# 4_TB6612_1_schdoc.net
KiCad netlist of a schematic drawn in Altium Designer
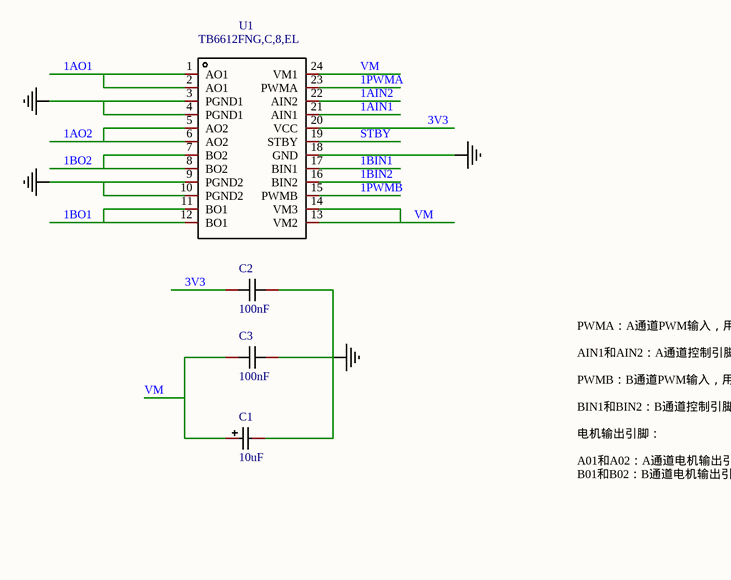
[diagram p0: 4_TB6612（1）.schdoc.schdoc]

(export (version "E")
  (design (tool "Eeschema 10.0.6"))
  (components
    (comp (ref "C1")
      (value "10uF")
      (fields
        (field (name "NAME") "10uF")
        (field (name "MANUFACTURER") "Kyocera AVX")
        (field (name "MANUFACTURER PART") "TAJB106K025RNJ")
        (field (name "TOLERANCE") "±10%")
      )
      (libsource (lib "altium-import") (part "root_2_TAJB106K025RNJ_"))
    )
    (comp (ref "C2")
      (value "100nF")
      (fields (field (name "NAME") "100nF"))
      (libsource (lib "altium-import") (part "root_0_CAP_0603_"))
    )
    (comp (ref "C3")
      (value "100nF")
      (fields (field (name "NAME") "100nF"))
      (libsource (lib "altium-import") (part "root_0_CAP_0603_"))
    )
    (comp (ref "U1")
      (value "TB6612FNG,C,8,EL")
      (description "驱动电机类型:有刷直流电机;电源电压:2.7V~5.5V;输出电流:1A;接口:并行;")
      (fields (field (name "NAME") "TB6612FNG,C,8,EL") (field (name "MANUFACTURER") "TOSHIBA(东芝)"))
      (libsource (lib "altium-import") (part "root_0_TB6612FNG,C,8,EL_"))
    )
  )
  (nets
    (net (code "1") (name "/1AIN1") (class "Default")
      (node (ref "U1") (pin "21") (pinfunction "AIN1_21") (pintype "passive"))
    )
    (net (code "2") (name "/1AIN2") (class "Default")
      (node (ref "U1") (pin "22") (pinfunction "AIN2_22") (pintype "passive"))
    )
    (net (code "3") (name "/1AO1") (class "Default")
      (node (ref "U1") (pin "1") (pinfunction "AO1_1") (pintype "passive"))
      (node (ref "U1") (pin "2") (pinfunction "AO1_2") (pintype "passive"))
    )
    (net (code "4") (name "/1AO2") (class "Default")
      (node (ref "U1") (pin "5") (pinfunction "AO2_5") (pintype "passive"))
      (node (ref "U1") (pin "6") (pinfunction "AO2_6") (pintype "passive"))
    )
    (net (code "5") (name "/1BIN1") (class "Default")
      (node (ref "U1") (pin "17") (pinfunction "BIN1_17") (pintype "passive"))
    )
    (net (code "6") (name "/1BIN2") (class "Default")
      (node (ref "U1") (pin "16") (pinfunction "BIN2_16") (pintype "passive"))
    )
    (net (code "7") (name "/1BO1") (class "Default")
      (node (ref "U1") (pin "11") (pinfunction "BO1_11") (pintype "passive"))
      (node (ref "U1") (pin "12") (pinfunction "BO1_12") (pintype "passive"))
    )
    (net (code "8") (name "/1BO2") (class "Default")
      (node (ref "U1") (pin "7") (pinfunction "BO2_7") (pintype "passive"))
      (node (ref "U1") (pin "8") (pinfunction "BO2_8") (pintype "passive"))
    )
    (net (code "9") (name "/1PWMA") (class "Default")
      (node (ref "U1") (pin "23") (pinfunction "PWMA_23") (pintype "passive"))
    )
    (net (code "10") (name "/1PWMB") (class "Default")
      (node (ref "U1") (pin "15") (pinfunction "PWMB_15") (pintype "passive"))
    )
    (net (code "11") (name "/3V3") (class "Default")
      (node (ref "C2") (pin "1") (pinfunction "1_1") (pintype "passive"))
      (node (ref "U1") (pin "20") (pinfunction "VCC_20") (pintype "passive"))
    )
    (net (code "12") (name "/STBY") (class "Default")
      (node (ref "U1") (pin "19") (pinfunction "STBY_19") (pintype "passive"))
    )
    (net (code "13") (name "/VM") (class "Default")
      (node (ref "C1") (pin "1") (pinfunction "1_1") (pintype "passive"))
      (node (ref "C3") (pin "1") (pinfunction "1_1") (pintype "passive"))
      (node (ref "U1") (pin "13") (pinfunction "VM2_13") (pintype "passive"))
      (node (ref "U1") (pin "14") (pinfunction "VM3_14") (pintype "passive"))
      (node (ref "U1") (pin "24") (pinfunction "VM1_24") (pintype "passive"))
    )
    (net (code "14") (name "<NO NET>") (class "Default")
      (node (ref "C1") (pin "2") (pinfunction "2_2") (pintype "passive"))
      (node (ref "C2") (pin "2") (pinfunction "2_2") (pintype "passive"))
      (node (ref "C3") (pin "2") (pinfunction "2_2") (pintype "passive"))
      (node (ref "U1") (pin "10") (pinfunction "PGND2_10") (pintype "passive"))
      (node (ref "U1") (pin "18") (pinfunction "GND_18") (pintype "passive"))
      (node (ref "U1") (pin "3") (pinfunction "PGND1_3") (pintype "passive"))
      (node (ref "U1") (pin "4") (pinfunction "PGND1_4") (pintype "passive"))
      (node (ref "U1") (pin "9") (pinfunction "PGND2_9") (pintype "passive"))
    )
  )
)
